# XTAG4.net
KiCad netlist of a schematic drawn in Altium Designer
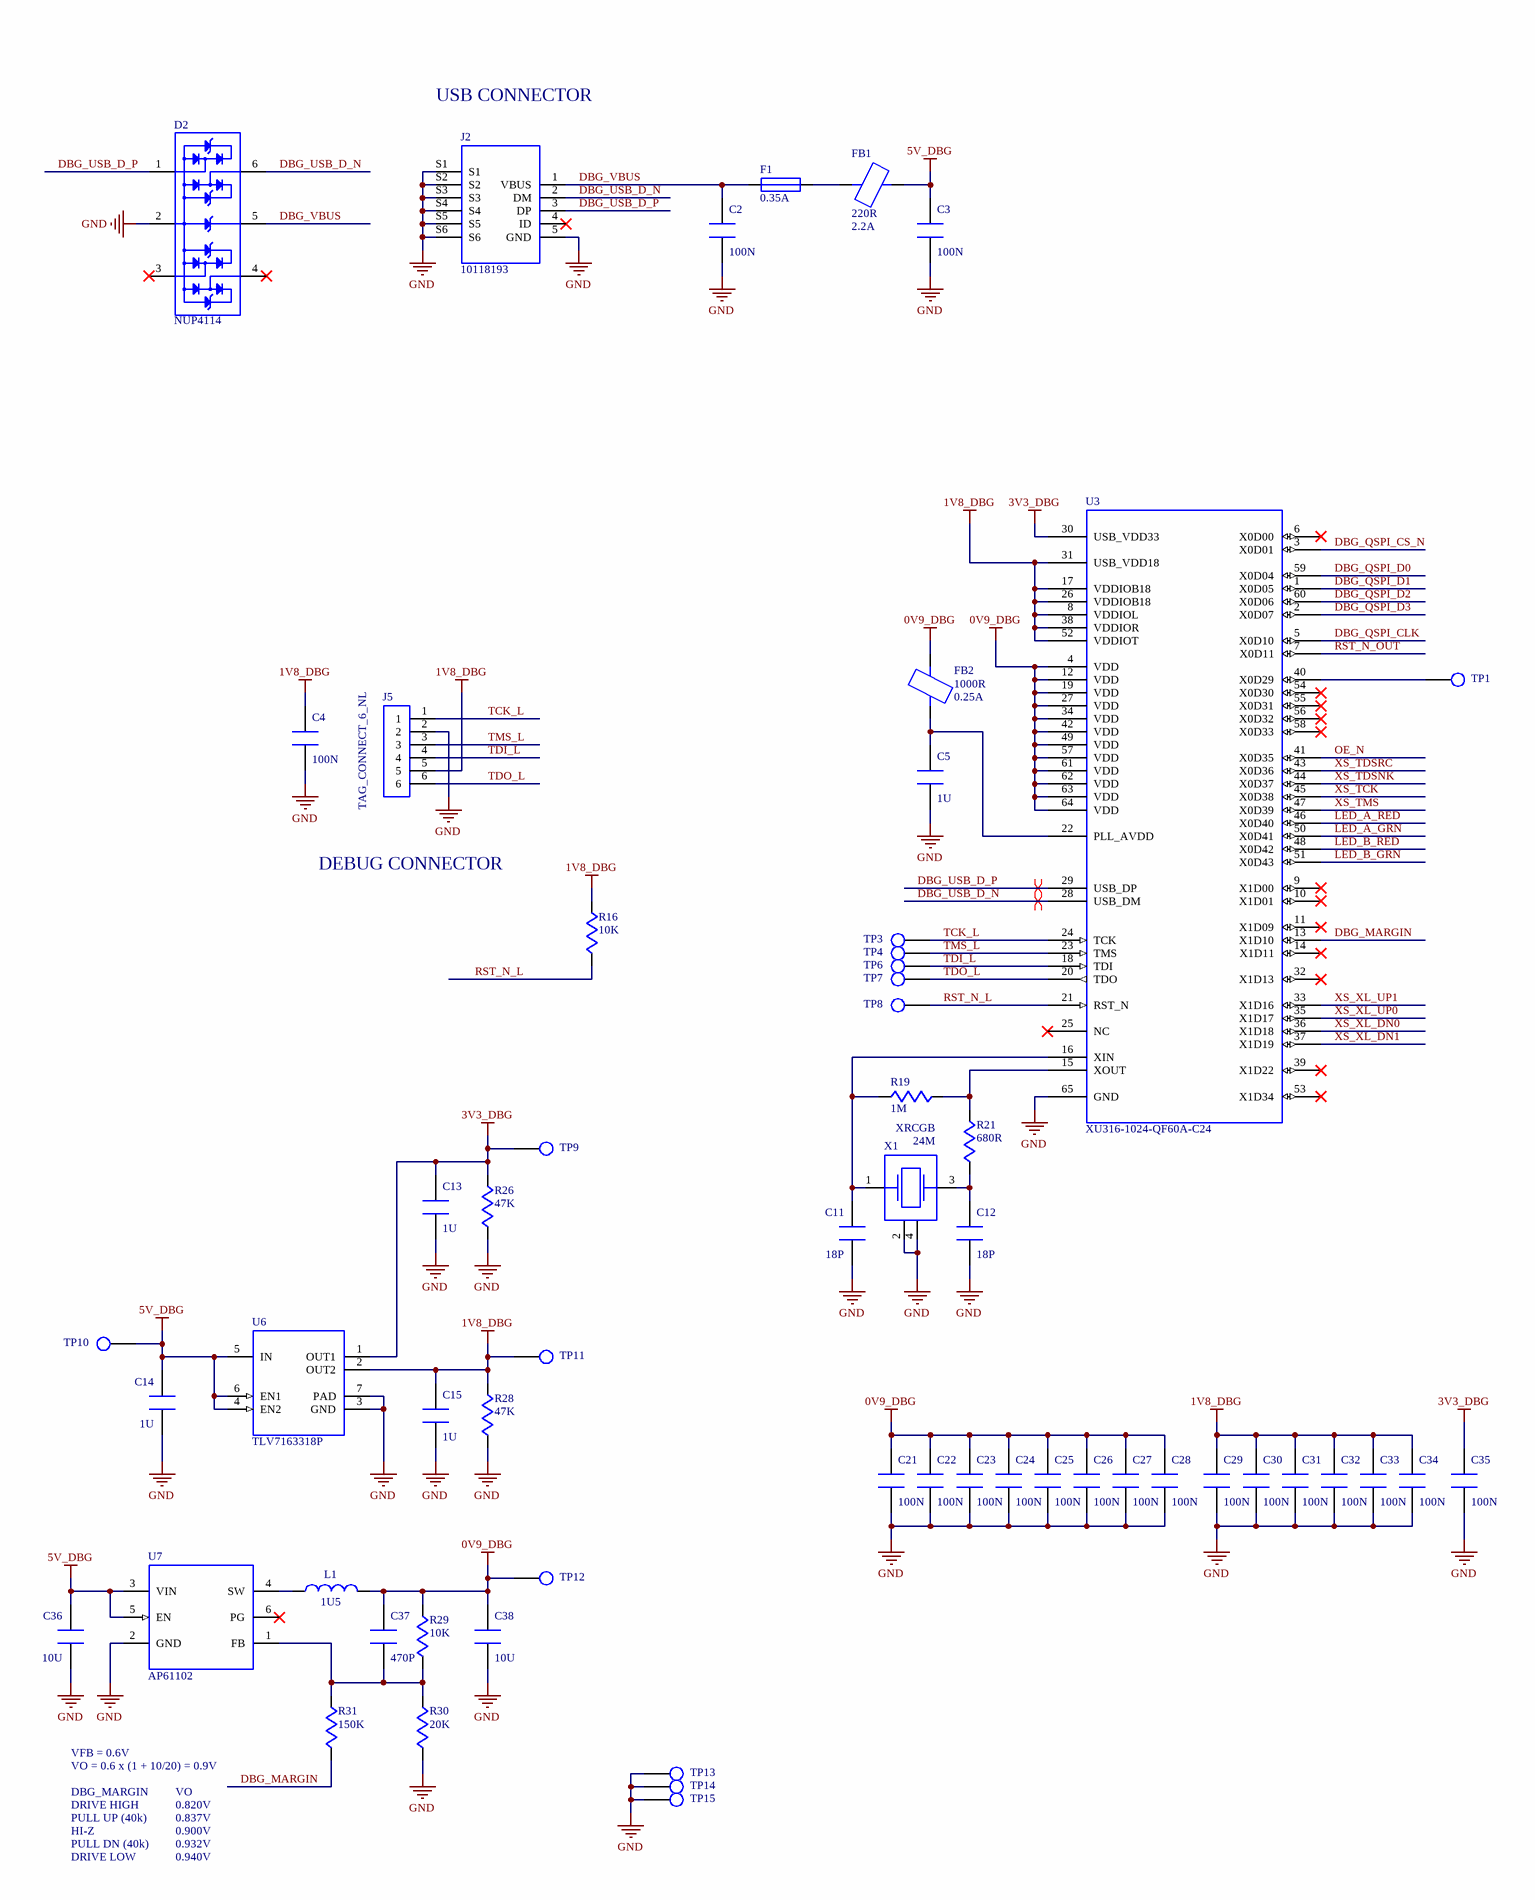
[diagram p0: XTAG4.SchDoc, left]
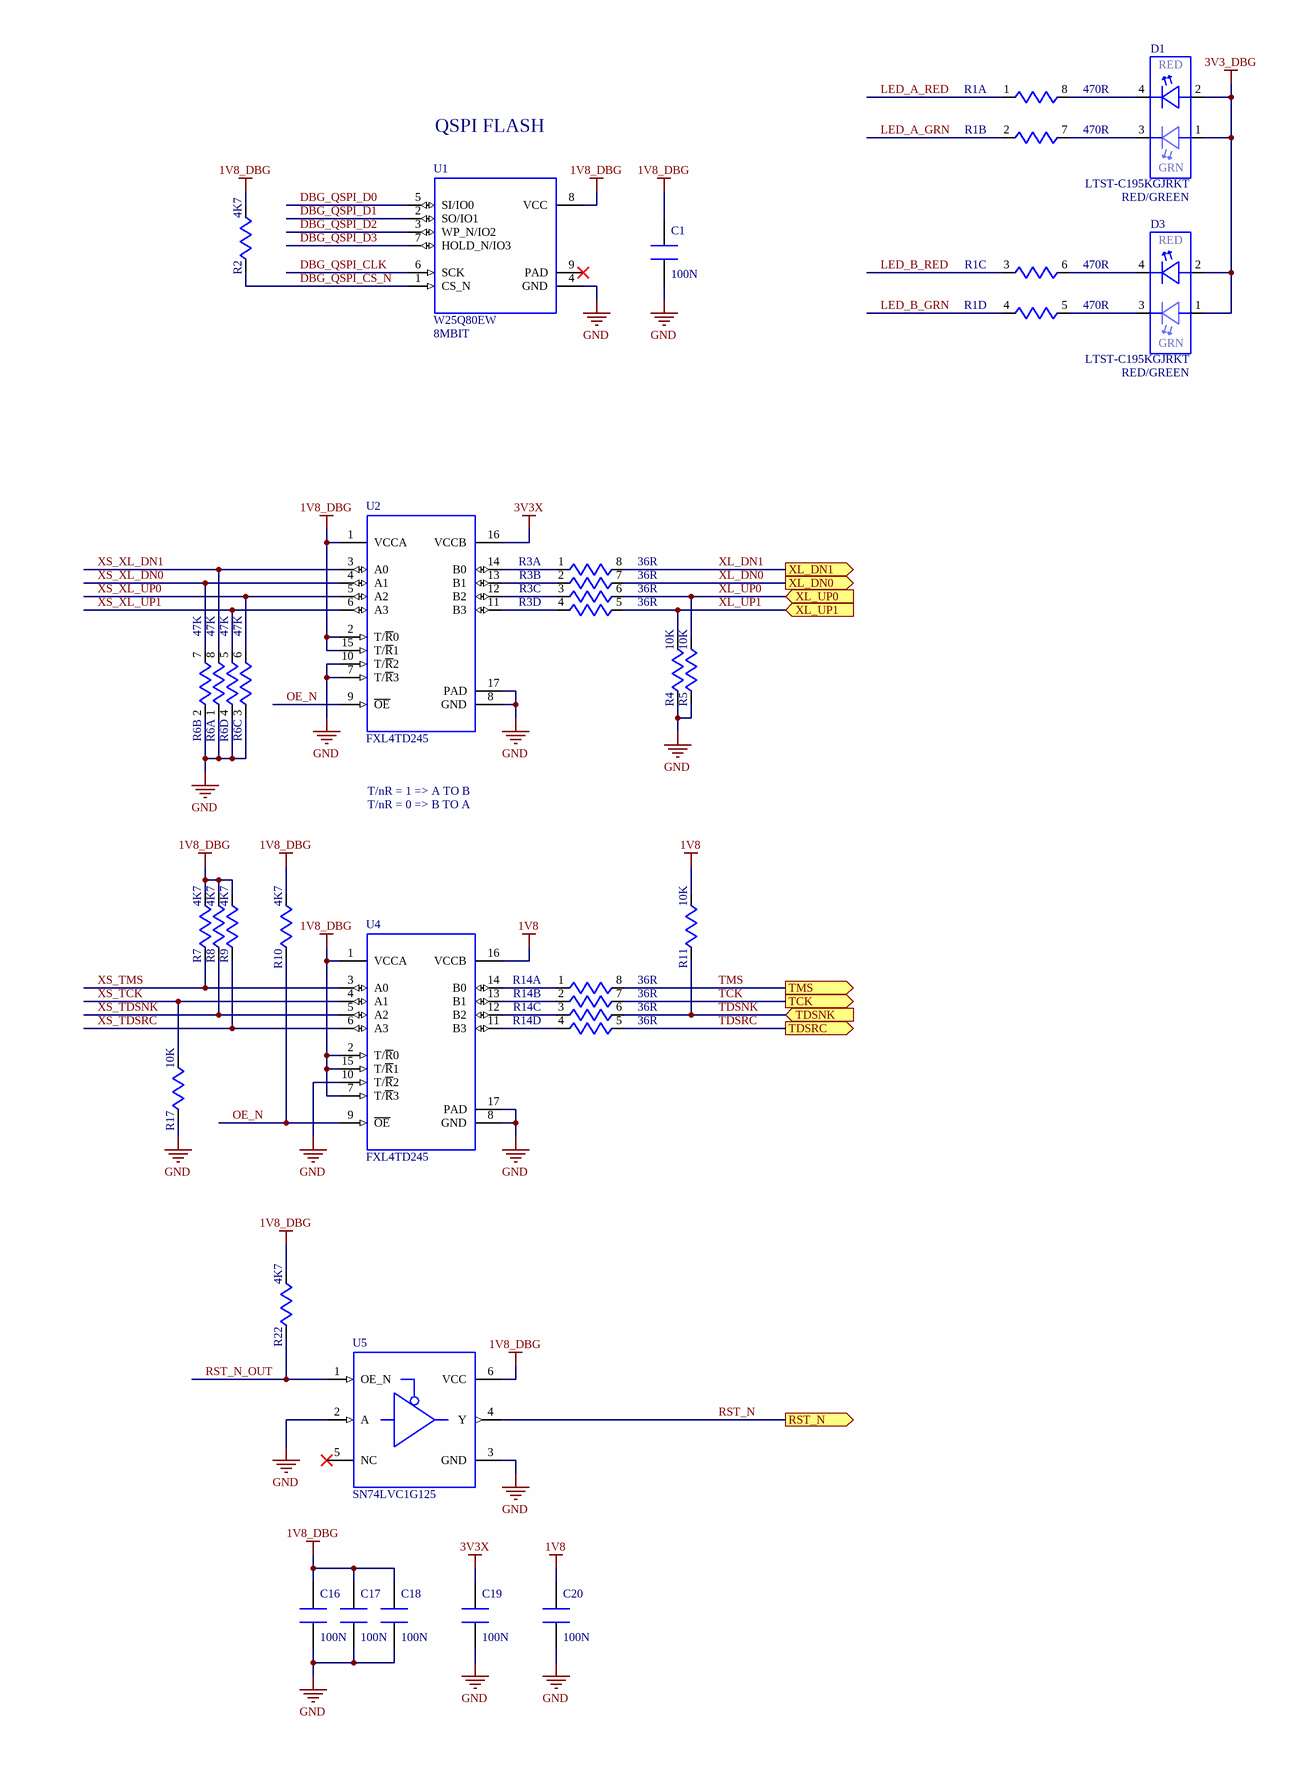
[diagram p1: XTAG4.SchDoc, right]

(export (version "E")
  (design (tool "Eeschema 10.0.6"))
  (components
    (comp (ref "C1")
      (value "100N")
      (footprint "CAPC1005X55N")
      (description "CHIP CAPACITOR, CERAMIC, 100NF, 16V, 10%, X7R, 0402")
      (fields (field (name "PART NUMBER") "STD-06-0048") (field (name "TOLERANCE") "10%"))
      (libsource (lib "JG_StandardLibrary") (part "CAP_NP"))
    )
    (comp (ref "C2")
      (value "100N")
      (footprint "CAPC1005X55N")
      (description "CHIP CAPACITOR, CERAMIC, 100NF, 16V, 10%, X7R, 0402")
      (fields (field (name "PART NUMBER") "STD-06-0048") (field (name "TOLERANCE") "10%"))
      (libsource (lib "JG_StandardLibrary") (part "CAP_NP"))
    )
    (comp (ref "C3")
      (value "100N")
      (footprint "CAPC1005X55N")
      (description "CHIP CAPACITOR, CERAMIC, 100NF, 16V, 10%, X7R, 0402")
      (fields (field (name "PART NUMBER") "STD-06-0048") (field (name "TOLERANCE") "10%"))
      (libsource (lib "JG_StandardLibrary") (part "CAP_NP"))
    )
    (comp (ref "C4")
      (value "100N")
      (footprint "CAPC1005X55N")
      (description "CHIP CAPACITOR, CERAMIC, 100NF, 16V, 10%, X7R, 0402")
      (fields (field (name "PART NUMBER") "STD-06-0048") (field (name "TOLERANCE") "10%"))
      (libsource (lib "JG_StandardLibrary") (part "CAP_NP"))
    )
    (comp (ref "C5")
      (value "1U")
      (footprint "CAPC1005X55N")
      (description "CHIP CAPACITOR, CERAMIC, 1.0UF, 16V, 10%, X5R, 0402")
      (fields (field (name "PART NUMBER") "STD-06-0140") (field (name "TOLERANCE") "20%"))
      (libsource (lib "JG_StandardLibrary") (part "CAP_NP"))
    )
    (comp (ref "C11")
      (value "18P")
      (footprint "CAPC1005X55N")
      (description "CHIP CAPACITOR, CERAMIC, 18PF, 50V, 5%, NP0, 0402")
      (fields (field (name "PART NUMBER") "STD-06-0016") (field (name "TOLERANCE") "5%"))
      (libsource (lib "JG_StandardLibrary") (part "CAP_NP"))
    )
    (comp (ref "C12")
      (value "18P")
      (footprint "CAPC1005X55N")
      (description "CHIP CAPACITOR, CERAMIC, 18PF, 50V, 5%, NP0, 0402")
      (fields (field (name "PART NUMBER") "STD-06-0016") (field (name "TOLERANCE") "5%"))
      (libsource (lib "JG_StandardLibrary") (part "CAP_NP"))
    )
    (comp (ref "C13")
      (value "1U")
      (footprint "CAPC1005X55N")
      (description "CHIP CAPACITOR, CERAMIC, 1.0UF, 16V, 10%, X5R, 0402")
      (fields (field (name "PART NUMBER") "STD-06-0140") (field (name "TOLERANCE") "20%"))
      (libsource (lib "JG_StandardLibrary") (part "CAP_NP"))
    )
    (comp (ref "C14")
      (value "1U")
      (footprint "CAPC1005X55N")
      (description "CHIP CAPACITOR, CERAMIC, 1.0UF, 16V, 10%, X5R, 0402")
      (fields (field (name "PART NUMBER") "STD-06-0140") (field (name "TOLERANCE") "20%"))
      (libsource (lib "JG_StandardLibrary") (part "CAP_NP"))
    )
    (comp (ref "C15")
      (value "1U")
      (footprint "CAPC1005X55N")
      (description "CHIP CAPACITOR, CERAMIC, 1.0UF, 16V, 10%, X5R, 0402")
      (fields (field (name "PART NUMBER") "STD-06-0140") (field (name "TOLERANCE") "20%"))
      (libsource (lib "JG_StandardLibrary") (part "CAP_NP"))
    )
    (comp (ref "C16")
      (value "100N")
      (footprint "CAPC1005X55N")
      (description "CHIP CAPACITOR, CERAMIC, 100NF, 16V, 10%, X7R, 0402")
      (fields (field (name "PART NUMBER") "STD-06-0048") (field (name "TOLERANCE") "10%"))
      (libsource (lib "JG_StandardLibrary") (part "CAP_NP"))
    )
    (comp (ref "C17")
      (value "100N")
      (footprint "CAPC1005X55N")
      (description "CHIP CAPACITOR, CERAMIC, 100NF, 16V, 10%, X7R, 0402")
      (fields (field (name "PART NUMBER") "STD-06-0048") (field (name "TOLERANCE") "10%"))
      (libsource (lib "JG_StandardLibrary") (part "CAP_NP"))
    )
    (comp (ref "C18")
      (value "100N")
      (footprint "CAPC1005X55N")
      (description "CHIP CAPACITOR, CERAMIC, 100NF, 16V, 10%, X7R, 0402")
      (fields (field (name "PART NUMBER") "STD-06-0048") (field (name "TOLERANCE") "10%"))
      (libsource (lib "JG_StandardLibrary") (part "CAP_NP"))
    )
    (comp (ref "C19")
      (value "100N")
      (footprint "CAPC1005X55N")
      (description "CHIP CAPACITOR, CERAMIC, 100NF, 16V, 10%, X7R, 0402")
      (fields (field (name "PART NUMBER") "STD-06-0048") (field (name "TOLERANCE") "10%"))
      (libsource (lib "JG_StandardLibrary") (part "CAP_NP"))
    )
    (comp (ref "C20")
      (value "100N")
      (footprint "CAPC1005X55N")
      (description "CHIP CAPACITOR, CERAMIC, 100NF, 16V, 10%, X7R, 0402")
      (fields (field (name "PART NUMBER") "STD-06-0048") (field (name "TOLERANCE") "10%"))
      (libsource (lib "JG_StandardLibrary") (part "CAP_NP"))
    )
    (comp (ref "C21")
      (value "100N")
      (footprint "CAPC1005X55N")
      (description "CHIP CAPACITOR, CERAMIC, 100NF, 16V, 10%, X7R, 0402")
      (fields (field (name "PART NUMBER") "STD-06-0048") (field (name "TOLERANCE") "10%"))
      (libsource (lib "JG_StandardLibrary") (part "CAP_NP"))
    )
    (comp (ref "C22")
      (value "100N")
      (footprint "CAPC1005X55N")
      (description "CHIP CAPACITOR, CERAMIC, 100NF, 16V, 10%, X7R, 0402")
      (fields (field (name "PART NUMBER") "STD-06-0048") (field (name "TOLERANCE") "10%"))
      (libsource (lib "JG_StandardLibrary") (part "CAP_NP"))
    )
    (comp (ref "C23")
      (value "100N")
      (footprint "CAPC1005X55N")
      (description "CHIP CAPACITOR, CERAMIC, 100NF, 16V, 10%, X7R, 0402")
      (fields (field (name "PART NUMBER") "STD-06-0048") (field (name "TOLERANCE") "10%"))
      (libsource (lib "JG_StandardLibrary") (part "CAP_NP"))
    )
    (comp (ref "C24")
      (value "100N")
      (footprint "CAPC1005X55N")
      (description "CHIP CAPACITOR, CERAMIC, 100NF, 16V, 10%, X7R, 0402")
      (fields (field (name "PART NUMBER") "STD-06-0048") (field (name "TOLERANCE") "10%"))
      (libsource (lib "JG_StandardLibrary") (part "CAP_NP"))
    )
    (comp (ref "C25")
      (value "100N")
      (footprint "CAPC1005X55N")
      (description "CHIP CAPACITOR, CERAMIC, 100NF, 16V, 10%, X7R, 0402")
      (fields (field (name "PART NUMBER") "STD-06-0048") (field (name "TOLERANCE") "10%"))
      (libsource (lib "JG_StandardLibrary") (part "CAP_NP"))
    )
    (comp (ref "C26")
      (value "100N")
      (footprint "CAPC1005X55N")
      (description "CHIP CAPACITOR, CERAMIC, 100NF, 16V, 10%, X7R, 0402")
      (fields (field (name "PART NUMBER") "STD-06-0048") (field (name "TOLERANCE") "10%"))
      (libsource (lib "JG_StandardLibrary") (part "CAP_NP"))
    )
    (comp (ref "C27")
      (value "100N")
      (footprint "CAPC1005X55N")
      (description "CHIP CAPACITOR, CERAMIC, 100NF, 16V, 10%, X7R, 0402")
      (fields (field (name "PART NUMBER") "STD-06-0048") (field (name "TOLERANCE") "10%"))
      (libsource (lib "JG_StandardLibrary") (part "CAP_NP"))
    )
    (comp (ref "C28")
      (value "100N")
      (footprint "CAPC1005X55N")
      (description "CHIP CAPACITOR, CERAMIC, 100NF, 16V, 10%, X7R, 0402")
      (fields (field (name "PART NUMBER") "STD-06-0048") (field (name "TOLERANCE") "10%"))
      (libsource (lib "JG_StandardLibrary") (part "CAP_NP"))
    )
    (comp (ref "C29")
      (value "100N")
      (footprint "CAPC1005X55N")
      (description "CHIP CAPACITOR, CERAMIC, 100NF, 16V, 10%, X7R, 0402")
      (fields (field (name "PART NUMBER") "STD-06-0048") (field (name "TOLERANCE") "10%"))
      (libsource (lib "JG_StandardLibrary") (part "CAP_NP"))
    )
    (comp (ref "C30")
      (value "100N")
      (footprint "CAPC1005X55N")
      (description "CHIP CAPACITOR, CERAMIC, 100NF, 16V, 10%, X7R, 0402")
      (fields (field (name "PART NUMBER") "STD-06-0048") (field (name "TOLERANCE") "10%"))
      (libsource (lib "JG_StandardLibrary") (part "CAP_NP"))
    )
    (comp (ref "C31")
      (value "100N")
      (footprint "CAPC1005X55N")
      (description "CHIP CAPACITOR, CERAMIC, 100NF, 16V, 10%, X7R, 0402")
      (fields (field (name "PART NUMBER") "STD-06-0048") (field (name "TOLERANCE") "10%"))
      (libsource (lib "JG_StandardLibrary") (part "CAP_NP"))
    )
    (comp (ref "C32")
      (value "100N")
      (footprint "CAPC1005X55N")
      (description "CHIP CAPACITOR, CERAMIC, 100NF, 16V, 10%, X7R, 0402")
      (fields (field (name "PART NUMBER") "STD-06-0048") (field (name "TOLERANCE") "10%"))
      (libsource (lib "JG_StandardLibrary") (part "CAP_NP"))
    )
    (comp (ref "C33")
      (value "100N")
      (footprint "CAPC1005X55N")
      (description "CHIP CAPACITOR, CERAMIC, 100NF, 16V, 10%, X7R, 0402")
      (fields (field (name "PART NUMBER") "STD-06-0048") (field (name "TOLERANCE") "10%"))
      (libsource (lib "JG_StandardLibrary") (part "CAP_NP"))
    )
    (comp (ref "C34")
      (value "100N")
      (footprint "CAPC1005X55N")
      (description "CHIP CAPACITOR, CERAMIC, 100NF, 16V, 10%, X7R, 0402")
      (fields (field (name "PART NUMBER") "STD-06-0048") (field (name "TOLERANCE") "10%"))
      (libsource (lib "JG_StandardLibrary") (part "CAP_NP"))
    )
    (comp (ref "C35")
      (value "100N")
      (footprint "CAPC1005X55N")
      (description "CHIP CAPACITOR, CERAMIC, 100NF, 16V, 10%, X7R, 0402")
      (fields (field (name "PART NUMBER") "STD-06-0048") (field (name "TOLERANCE") "10%"))
      (libsource (lib "JG_StandardLibrary") (part "CAP_NP"))
    )
    (comp (ref "C36")
      (value "10U")
      (footprint "CAPC1608X90N")
      (description "CHIP CAPACITOR, CERAMIC, 10UF, 10V, 20%, X5R, 0603")
      (fields (field (name "PART NUMBER") "GEN-03-0043") (field (name "TOLERANCE") "20%"))
      (libsource (lib "JG_GeneralLibrary") (part "CAP_NP"))
    )
    (comp (ref "C37")
      (value "470P")
      (footprint "CAPC1005X55N")
      (description "CHIP CAPACITOR, CERAMIC, 470PF, 50V, 10%, X7R, 0402")
      (fields (field (name "PART NUMBER") "STD-06-0034") (field (name "TOLERANCE") "10%"))
      (libsource (lib "JG_StandardLibrary") (part "CAP_NP"))
    )
    (comp (ref "C38")
      (value "10U")
      (footprint "CAPC1608X90N")
      (description "CHIP CAPACITOR, CERAMIC, 10UF, 10V, 20%, X5R, 0603")
      (fields (field (name "PART NUMBER") "GEN-03-0043") (field (name "TOLERANCE") "20%"))
      (libsource (lib "JG_GeneralLibrary") (part "CAP_NP"))
    )
    (comp (ref "D1")
      (value "LTST-C195KGJRKT")
      (footprint "LED_LITEON_LTST_C195KGJRKT")
      (description "LED, Top View, RED/GREEN, SMD, 0606")
      (fields
        (field (name "PART NUMBER") "GEN-17-0007")
        (field (name "COLOUR") "RED/GREEN")
        (field (name "MANUFACTURER") "Lite-On")
      )
      (libsource (lib "JG_GeneralLibrary") (part "LED_DUAL_SEPARATE_A"))
    )
    (comp (ref "D2")
      (value "NUP4114")
      (footprint "SOT65P210X110-6N")
      (description "ESD Protection Diode Array, 0.6pF, SC-70-6 (SC-88)")
      (fields (field (name "PART NUMBER") "GEN-16-0048") (field (name "MANUFACTURER") "ON Semiconductor"))
      (libsource (lib "JG_GeneralLibrary") (part "DIODE_QUAD_ESD_C"))
    )
    (comp (ref "D3")
      (value "LTST-C195KGJRKT")
      (footprint "LED_LITEON_LTST_C195KGJRKT")
      (description "LED, Top View, RED/GREEN, SMD, 0606")
      (fields
        (field (name "PART NUMBER") "GEN-17-0007")
        (field (name "COLOUR") "RED/GREEN")
        (field (name "MANUFACTURER") "Lite-On")
      )
      (libsource (lib "JG_GeneralLibrary") (part "LED_DUAL_SEPARATE_A"))
    )
    (comp (ref "F1")
      (value "0.35A")
      (footprint "FUSC215X135X75L40N")
      (description "PTC Fuse, SMD, 0.35A hold, 0.75A trip, 6V, 0805")
      (fields (field (name "PART NUMBER") "GEN-21-0009") (field (name "MANUFACTURER") "Bel Fuse"))
      (libsource (lib "JG_GeneralLibrary") (part "FUSE"))
    )
    (comp (ref "FB1")
      (value "220R")
      (footprint "INDC1608X95N")
      (description "Ferrite Bead, 220R AT 100MHz, For Power Lines, AEC-Q200, 0603, 2.2A")
      (fields
        (field (name "PART NUMBER") "GEN-04-0018")
        (field (name "RATED CURRENT") "2.2A")
        (field (name "MANUFACTURER") "Murata")
      )
      (libsource (lib "JG_GeneralLibrary") (part "FERRITE"))
    )
    (comp (ref "FB2")
      (value "1000R")
      (footprint "INDC1005X55N")
      (description "Ferrite Bead, 1000R AT 100MHz, For Signal Lines, 0402, 0.25A")
      (fields
        (field (name "PART NUMBER") "GEN-04-0019")
        (field (name "RATED CURRENT") "0.25A")
        (field (name "MANUFACTURER") "Murata")
      )
      (libsource (lib "JG_GeneralLibrary") (part "FERRITE"))
    )
    (comp (ref "J2")
      (value "10118193")
      (footprint "CON_FCI_10118193")
      (description "USB Micro B Receptacle, Right Angle, SMD w/2 DIP Legs")
      (fields (field (name "PART NUMBER") "GEN-01-0020") (field (name "MANUFACTURER") "FCI"))
      (libsource (lib "JG_GeneralLibrary") (part "FCI_10118193"))
    )
    (comp (ref "J5")
      (value "TAG_CONNECT_6_NL")
      (footprint "CON_TAG_CONNECT_6_NOLEG")
      (description "Connectorless Tag Connect Footprint, 6 pin, No Legs")
      (fields (field (name "PART NUMBER") "GEN-24-0021") (field (name "MANUFACTURER") "NA"))
      (libsource (lib "JG_GeneralLibrary") (part "CON_6PIN_NOBOM"))
    )
    (comp (ref "L1")
      (value "1U5")
      (footprint "INDC2520X120N")
      (description "Power Inductor, 1.5uH, 2.6A, 65mR DCR, 2.5x2.0x1.2mm, SMD")
      (fields (field (name "PART NUMBER") "GEN-05-0025") (field (name "TOLERANCE") "20%"))
      (libsource (lib "JG_GeneralLibrary") (part "INDUCTOR"))
    )
    (comp (ref "R1")
      (value "470R")
      (footprint "RESCAXS50P200X100X55-8N")
      (description "CHIP RESISTOR ARRAY, 4 ELEMENT, 470 OHM, 63mW, 5%, 0804")
      (fields (field (name "PART NUMBER") "STD-09-0014") (field (name "TOLERANCE") "5%"))
      (libsource (lib "JG_StandardLibrary") (part "RES_NET_4_A"))
    )
    (comp (ref "R2")
      (value "4K7")
      (footprint "RESC1005X40N")
      (description "CHIP RESISTOR, 4.7K OHM, 63mW, 1%, 0402")
      (fields (field (name "PART NUMBER") "STD-01-0072") (field (name "TOLERANCE") "1%"))
      (libsource (lib "JG_StandardLibrary") (part "RES"))
    )
    (comp (ref "R3")
      (value "36R")
      (footprint "RESCAXS50P200X100X55-8N")
      (description "CHIP RESISTOR ARRAY, 4 ELEMENT, 36 OHM, 63mW, 5%, 0804")
      (fields (field (name "PART NUMBER") "GEN-02-0026") (field (name "TOLERANCE") "5%"))
      (libsource (lib "JG_GeneralLibrary") (part "RES_NET_4_A"))
    )
    (comp (ref "R4")
      (value "10K")
      (footprint "RESC1005X40N")
      (description "CHIP RESISTOR, 10K OHM, 63mW, 1%, 0402")
      (fields (field (name "PART NUMBER") "STD-01-0080") (field (name "TOLERANCE") "1%"))
      (libsource (lib "JG_StandardLibrary") (part "RES"))
    )
    (comp (ref "R5")
      (value "10K")
      (footprint "RESC1005X40N")
      (description "CHIP RESISTOR, 10K OHM, 63mW, 1%, 0402")
      (fields (field (name "PART NUMBER") "STD-01-0080") (field (name "TOLERANCE") "1%"))
      (libsource (lib "JG_StandardLibrary") (part "RES"))
    )
    (comp (ref "R6")
      (value "47K")
      (footprint "RESCAXS50P200X100X55-8N")
      (description "CHIP RESISTOR ARRAY, 4 ELEMENT, 47K OHM, 63mW, 5%, 0804")
      (fields (field (name "PART NUMBER") "STD-09-0026") (field (name "TOLERANCE") "5%"))
      (libsource (lib "JG_StandardLibrary") (part "RES_NET_4_A"))
    )
    (comp (ref "R7")
      (value "4K7")
      (footprint "RESC1005X40N")
      (description "CHIP RESISTOR, 4.7K OHM, 63mW, 1%, 0402")
      (fields (field (name "PART NUMBER") "STD-01-0072") (field (name "TOLERANCE") "1%"))
      (libsource (lib "JG_StandardLibrary") (part "RES"))
    )
    (comp (ref "R8")
      (value "4K7")
      (footprint "RESC1005X40N")
      (description "CHIP RESISTOR, 4.7K OHM, 63mW, 1%, 0402")
      (fields (field (name "PART NUMBER") "STD-01-0072") (field (name "TOLERANCE") "1%"))
      (libsource (lib "JG_StandardLibrary") (part "RES"))
    )
    (comp (ref "R9")
      (value "4K7")
      (footprint "RESC1005X40N")
      (description "CHIP RESISTOR, 4.7K OHM, 63mW, 1%, 0402")
      (fields (field (name "PART NUMBER") "STD-01-0072") (field (name "TOLERANCE") "1%"))
      (libsource (lib "JG_StandardLibrary") (part "RES"))
    )
    (comp (ref "R10")
      (value "4K7")
      (footprint "RESC1005X40N")
      (description "CHIP RESISTOR, 4.7K OHM, 63mW, 1%, 0402")
      (fields (field (name "PART NUMBER") "STD-01-0072") (field (name "TOLERANCE") "1%"))
      (libsource (lib "JG_StandardLibrary") (part "RES"))
    )
    (comp (ref "R11")
      (value "10K")
      (footprint "RESC1005X40N")
      (description "CHIP RESISTOR, 10K OHM, 63mW, 1%, 0402")
      (fields (field (name "PART NUMBER") "STD-01-0080") (field (name "TOLERANCE") "1%"))
      (libsource (lib "JG_StandardLibrary") (part "RES"))
    )
    (comp (ref "R14")
      (value "36R")
      (footprint "RESCAXS50P200X100X55-8N")
      (description "CHIP RESISTOR ARRAY, 4 ELEMENT, 36 OHM, 63mW, 5%, 0804")
      (fields (field (name "PART NUMBER") "GEN-02-0026") (field (name "TOLERANCE") "5%"))
      (libsource (lib "JG_GeneralLibrary") (part "RES_NET_4_A"))
    )
    (comp (ref "R16")
      (value "10K")
      (footprint "RESC1005X40N")
      (description "CHIP RESISTOR, 10K OHM, 63mW, 1%, 0402")
      (fields (field (name "PART NUMBER") "STD-01-0080") (field (name "TOLERANCE") "1%"))
      (libsource (lib "JG_StandardLibrary") (part "RES"))
    )
    (comp (ref "R17")
      (value "10K")
      (footprint "RESC1005X40N")
      (description "CHIP RESISTOR, 10K OHM, 63mW, 1%, 0402")
      (fields (field (name "PART NUMBER") "STD-01-0080") (field (name "TOLERANCE") "1%"))
      (libsource (lib "JG_StandardLibrary") (part "RES"))
    )
    (comp (ref "R19")
      (value "1M")
      (footprint "RESC1005X40N")
      (description "CHIP RESISTOR, 1.0M OHM, 63mW, 5%, 0402")
      (fields (field (name "PART NUMBER") "STD-01-0128") (field (name "TOLERANCE") "5%"))
      (libsource (lib "JG_StandardLibrary") (part "RES"))
    )
    (comp (ref "R21")
      (value "680R")
      (footprint "RESC1005X40N")
      (description "CHIP RESISTOR, 680 OHM, 63mW, 1%, 0402")
      (fields (field (name "PART NUMBER") "STD-01-0052") (field (name "TOLERANCE") "1%"))
      (libsource (lib "JG_StandardLibrary") (part "RES"))
    )
    (comp (ref "R22")
      (value "4K7")
      (footprint "RESC1005X40N")
      (description "CHIP RESISTOR, 4.7K OHM, 63mW, 1%, 0402")
      (fields (field (name "PART NUMBER") "STD-01-0072") (field (name "TOLERANCE") "1%"))
      (libsource (lib "JG_StandardLibrary") (part "RES"))
    )
    (comp (ref "R26")
      (value "47K")
      (footprint "RESC1005X40N")
      (description "CHIP RESISTOR, 47K OHM, 63mW, 1%, 0402")
      (fields (field (name "PART NUMBER") "STD-01-0096") (field (name "TOLERANCE") "1%"))
      (libsource (lib "JG_StandardLibrary") (part "RES"))
    )
    (comp (ref "R28")
      (value "47K")
      (footprint "RESC1005X40N")
      (description "CHIP RESISTOR, 47K OHM, 63mW, 1%, 0402")
      (fields (field (name "PART NUMBER") "STD-01-0096") (field (name "TOLERANCE") "1%"))
      (libsource (lib "JG_StandardLibrary") (part "RES"))
    )
    (comp (ref "R29")
      (value "10K")
      (footprint "RESC1005X40N")
      (description "CHIP RESISTOR, 10K OHM, 63mW, 1%, 0402")
      (fields (field (name "PART NUMBER") "STD-01-0080") (field (name "TOLERANCE") "1%"))
      (libsource (lib "JG_StandardLibrary") (part "RES"))
    )
    (comp (ref "R30")
      (value "20K")
      (footprint "RESC1005X40N")
      (description "CHIP RESISTOR, 20K OHM, 63mW, 1%, 0402")
      (fields (field (name "PART NUMBER") "STD-01-0087") (field (name "TOLERANCE") "1%"))
      (libsource (lib "JG_StandardLibrary") (part "RES"))
    )
    (comp (ref "R31")
      (value "150K")
      (footprint "RESC1005X40N")
      (description "CHIP RESISTOR, 150K OHM, 63mW, 1%, 0402")
      (fields (field (name "PART NUMBER") "STD-01-0108") (field (name "TOLERANCE") "1%"))
      (libsource (lib "JG_StandardLibrary") (part "RES"))
    )
    (comp (ref "TP1")
      (value "TESTPOINT")
      (footprint "TESTPOINT_SMD_1MM")
      (description "Testpoint, SMD, 1mm")
      (fields (field (name "PART NUMBER") "GEN-24-0003") (field (name "MANUFACTURER") "NA"))
      (libsource (lib "JG_GeneralLibrary") (part "TESTPOINT"))
    )
    (comp (ref "TP3")
      (value "TESTPOINT")
      (footprint "TESTPOINT_SMD_1.2MM")
      (description "Testpoint, SMD, 1.2mm")
      (fields (field (name "PART NUMBER") "GEN-24-0014") (field (name "MANUFACTURER") "NA"))
      (libsource (lib "JG_GeneralLibrary") (part "TESTPOINT"))
    )
    (comp (ref "TP4")
      (value "TESTPOINT")
      (footprint "TESTPOINT_SMD_1.2MM")
      (description "Testpoint, SMD, 1.2mm")
      (fields (field (name "PART NUMBER") "GEN-24-0014") (field (name "MANUFACTURER") "NA"))
      (libsource (lib "JG_GeneralLibrary") (part "TESTPOINT"))
    )
    (comp (ref "TP6")
      (value "TESTPOINT")
      (footprint "TESTPOINT_SMD_1.2MM")
      (description "Testpoint, SMD, 1.2mm")
      (fields (field (name "PART NUMBER") "GEN-24-0014") (field (name "MANUFACTURER") "NA"))
      (libsource (lib "JG_GeneralLibrary") (part "TESTPOINT"))
    )
    (comp (ref "TP7")
      (value "TESTPOINT")
      (footprint "TESTPOINT_SMD_1.2MM")
      (description "Testpoint, SMD, 1.2mm")
      (fields (field (name "PART NUMBER") "GEN-24-0014") (field (name "MANUFACTURER") "NA"))
      (libsource (lib "JG_GeneralLibrary") (part "TESTPOINT"))
    )
    (comp (ref "TP8")
      (value "TESTPOINT")
      (footprint "TESTPOINT_SMD_1.2MM")
      (description "Testpoint, SMD, 1.2mm")
      (fields (field (name "PART NUMBER") "GEN-24-0014") (field (name "MANUFACTURER") "NA"))
      (libsource (lib "JG_GeneralLibrary") (part "TESTPOINT"))
    )
    (comp (ref "TP9")
      (value "TESTPOINT")
      (footprint "TESTPOINT_SMD_1.2MM")
      (description "Testpoint, SMD, 1.2mm")
      (fields (field (name "PART NUMBER") "GEN-24-0014") (field (name "MANUFACTURER") "NA"))
      (libsource (lib "JG_GeneralLibrary") (part "TESTPOINT"))
    )
    (comp (ref "TP10")
      (value "TESTPOINT")
      (footprint "TESTPOINT_SMD_1.2MM")
      (description "Testpoint, SMD, 1.2mm")
      (fields (field (name "PART NUMBER") "GEN-24-0014") (field (name "MANUFACTURER") "NA"))
      (libsource (lib "JG_GeneralLibrary") (part "TESTPOINT"))
    )
    (comp (ref "TP11")
      (value "TESTPOINT")
      (footprint "TESTPOINT_SMD_1.2MM")
      (description "Testpoint, SMD, 1.2mm")
      (fields (field (name "PART NUMBER") "GEN-24-0014") (field (name "MANUFACTURER") "NA"))
      (libsource (lib "JG_GeneralLibrary") (part "TESTPOINT"))
    )
    (comp (ref "TP12")
      (value "TESTPOINT")
      (footprint "TESTPOINT_SMD_1.2MM")
      (description "Testpoint, SMD, 1.2mm")
      (fields (field (name "PART NUMBER") "GEN-24-0014") (field (name "MANUFACTURER") "NA"))
      (libsource (lib "JG_GeneralLibrary") (part "TESTPOINT"))
    )
    (comp (ref "TP13")
      (value "TESTPOINT")
      (footprint "TESTPOINT_SMD_1.2MM")
      (description "Testpoint, SMD, 1.2mm")
      (fields (field (name "PART NUMBER") "GEN-24-0014") (field (name "MANUFACTURER") "NA"))
      (libsource (lib "JG_GeneralLibrary") (part "TESTPOINT"))
    )
    (comp (ref "TP14")
      (value "TESTPOINT")
      (footprint "TESTPOINT_SMD_1.2MM")
      (description "Testpoint, SMD, 1.2mm")
      (fields (field (name "PART NUMBER") "GEN-24-0014") (field (name "MANUFACTURER") "NA"))
      (libsource (lib "JG_GeneralLibrary") (part "TESTPOINT"))
    )
    (comp (ref "TP15")
      (value "TESTPOINT")
      (footprint "TESTPOINT_SMD_1.2MM")
      (description "Testpoint, SMD, 1.2mm")
      (fields (field (name "PART NUMBER") "GEN-24-0014") (field (name "MANUFACTURER") "NA"))
      (libsource (lib "JG_GeneralLibrary") (part "TESTPOINT"))
    )
    (comp (ref "U1")
      (value "W25Q80EW")
      (footprint "SON9P50_200X300X60L45X25T160X20N")
      (description "Memory, Flash, SPI, Multi-IO, 8Mb (4Kx256), 1.65V to 1.95V, USON-8 (2x3mm)")
      (fields
        (field (name "PART NUMBER") "GEN-12-0023")
        (field (name "MEMORY SIZE") "8MBIT")
        (field (name "MANUFACTURER") "Winbond")
      )
      (libsource (lib "JG_GeneralLibrary") (part "SPI_FLASH_MULTI_C"))
    )
    (comp (ref "U2")
      (value "FXL4TD245")
      (footprint "IC_NXP_DHVQFN16")
      (description "Configurable Dual-Voltage Supply Translator, 4 bit, DQFN16")
      (fields (field (name "PART NUMBER") "GEN-11-0017") (field (name "MANUFACTURER") "Fairchild"))
      (libsource (lib "JG_GeneralLibrary") (part "FXL4TD245_A"))
    )
    (comp (ref "U3")
      (value "XU316-1024-QF60A-C24")
      (footprint "IC_XMOS_PX_QFN60A_NEWPADDLE")
      (description "Processor, xcore.ai, 2400MIPS, 1.8V VDDIO, 60QFN")
      (fields (field (name "PART NUMBER") "GEN-08-0033") (field (name "MANUFACTURER") "XMOS"))
      (libsource (lib "JG_GeneralLibrary") (part "XMOS_XU316_1024_QF60A"))
    )
    (comp (ref "U4")
      (value "FXL4TD245")
      (footprint "IC_NXP_DHVQFN16")
      (description "Configurable Dual-Voltage Supply Translator, 4 bit, DQFN16")
      (fields (field (name "PART NUMBER") "GEN-11-0017") (field (name "MANUFACTURER") "Fairchild"))
      (libsource (lib "JG_GeneralLibrary") (part "FXL4TD245_A"))
    )
    (comp (ref "U5")
      (value "SN74LVC1G125")
      (footprint "TI_R_PUSON_N6")
      (description "Single Buffer with 3-State Output, LVC Series, SON6")
      (fields (field (name "PART NUMBER") "GEN-11-0049") (field (name "MANUFACTURER") "Texas Instruments"))
      (libsource (lib "JG_GeneralLibrary") (part "SINGLEGATE_125_B"))
    )
    (comp (ref "U6")
      (value "TLV7163318P")
      (footprint "TI_S_PX2SON_N6")
      (description "Voltage Regulator, Dual, 3.3V/1.8V, 150mA, Low Iq, Low Dropout, X2SON-6")
      (fields (field (name "PART NUMBER") "GEN-14-0057") (field (name "MANUFACTURER") "Texas Instruments"))
      (libsource (lib "JG_GeneralLibrary") (part "VREG_FIXED_DUAL_6_A"))
    )
    (comp (ref "U7")
      (value "AP61102")
      (footprint "ICSOFL6P50_160X160X60L30X21N")
      (description "DC-DC Synchronous Buck Converter, Adjustable, PFM/PWM, Power Good, 2.2MHz, 1A, SOT563")
      (fields (field (name "PART NUMBER") "GEN-14-0064") (field (name "MANUFACTURER") "Diodes Incorporated"))
      (libsource (lib "JG_GeneralLibrary") (part "DIODES_AP61102"))
    )
    (comp (ref "X1")
      (value "XRCGB")
      (footprint "OSCCC200X160X70N")
      (description "Crystal, 24MHz, Freq Tol. ±8ppm, Freq Stab. ±12ppm, CL 10pF, Max ESR 70 Ohm, 2.0x1.6mm SMD")
      (fields
        (field (name "FREQUENCY") "24M")
        (field (name "PART NUMBER") "GEN-15-0038")
        (field (name "MANUFACTURER") "Murata")
      )
      (libsource (lib "JG_GeneralLibrary") (part "CRYSTAL_4PIN_A"))
    )
  )
  (nets
    (net (code "1") (name "/DBG_MARGIN") (class "Default")
      (node (ref "R31") (pin "1") (pinfunction "1_1") (pintype "passive"))
      (node (ref "U3") (pin "13") (pinfunction "X1D10_13") (pintype "bidirectional"))
    )
    (net (code "2") (name "/DBG_QSPI_CLK") (class "Default")
      (node (ref "U1") (pin "6") (pinfunction "SCK_6") (pintype "input"))
      (node (ref "U3") (pin "5") (pinfunction "X0D10_5") (pintype "bidirectional"))
    )
    (net (code "3") (name "/DBG_QSPI_CS_N") (class "Default")
      (node (ref "R2") (pin "1") (pinfunction "1_1") (pintype "passive"))
      (node (ref "U1") (pin "1") (pinfunction "CS_N_1") (pintype "input"))
      (node (ref "U3") (pin "3") (pinfunction "X0D01_3") (pintype "bidirectional"))
    )
    (net (code "4") (name "/DBG_QSPI_D0") (class "Default")
      (node (ref "U1") (pin "5") (pinfunction "SI/IO0_5") (pintype "bidirectional"))
      (node (ref "U3") (pin "59") (pinfunction "X0D04_59") (pintype "bidirectional"))
    )
    (net (code "5") (name "/DBG_QSPI_D1") (class "Default")
      (node (ref "U1") (pin "2") (pinfunction "SO/IO1_2") (pintype "bidirectional"))
      (node (ref "U3") (pin "1") (pinfunction "X0D05_1") (pintype "bidirectional"))
    )
    (net (code "6") (name "/DBG_QSPI_D2") (class "Default")
      (node (ref "U1") (pin "3") (pinfunction "WP_N/IO2_3") (pintype "bidirectional"))
      (node (ref "U3") (pin "60") (pinfunction "X0D06_60") (pintype "bidirectional"))
    )
    (net (code "7") (name "/DBG_QSPI_D3") (class "Default")
      (node (ref "U1") (pin "7") (pinfunction "HOLD_N/IO3_7") (pintype "bidirectional"))
      (node (ref "U3") (pin "2") (pinfunction "X0D07_2") (pintype "bidirectional"))
    )
    (net (code "8") (name "/DBG_USB_D_N") (class "Default")
      (node (ref "D2") (pin "6") (pinfunction "6_6") (pintype "passive"))
      (node (ref "J2") (pin "2") (pinfunction "DM_2") (pintype "passive"))
      (node (ref "U3") (pin "28") (pinfunction "USB_DM_28") (pintype "passive"))
    )
    (net (code "9") (name "/DBG_USB_D_P") (class "Default")
      (node (ref "D2") (pin "1") (pinfunction "1_1") (pintype "passive"))
      (node (ref "J2") (pin "3") (pinfunction "DP_3") (pintype "passive"))
      (node (ref "U3") (pin "29") (pinfunction "USB_DP_29") (pintype "passive"))
    )
    (net (code "10") (name "/DBG_VBUS") (class "Default")
      (node (ref "C2") (pin "1") (pinfunction "1_1") (pintype "passive"))
      (node (ref "D2") (pin "5") (pinfunction "5_5") (pintype "passive"))
      (node (ref "F1") (pin "1") (pinfunction "T1_1") (pintype "passive"))
      (node (ref "J2") (pin "1") (pinfunction "VBUS_1") (pintype "passive"))
    )
    (net (code "11") (name "/LED_A_GRN") (class "Default")
      (node (ref "R1") (pin "2") (pinfunction "2_2") (pintype "passive"))
      (node (ref "U3") (pin "50") (pinfunction "X0D41_50") (pintype "bidirectional"))
    )
    (net (code "12") (name "/LED_A_RED") (class "Default")
      (node (ref "R1") (pin "1") (pinfunction "1_1") (pintype "passive"))
      (node (ref "U3") (pin "46") (pinfunction "X0D40_46") (pintype "bidirectional"))
    )
    (net (code "13") (name "/LED_B_GRN") (class "Default")
      (node (ref "R1") (pin "4") (pinfunction "4_4") (pintype "passive"))
      (node (ref "U3") (pin "51") (pinfunction "X0D43_51") (pintype "bidirectional"))
    )
    (net (code "14") (name "/LED_B_RED") (class "Default")
      (node (ref "R1") (pin "3") (pinfunction "3_3") (pintype "passive"))
      (node (ref "U3") (pin "48") (pinfunction "X0D42_48") (pintype "bidirectional"))
    )
    (net (code "15") (name "/OE_N") (class "Default")
      (node (ref "R10") (pin "1") (pinfunction "1_1") (pintype "passive"))
      (node (ref "U2") (pin "9") (pinfunction "~{OE}_9") (pintype "input"))
      (node (ref "U3") (pin "41") (pinfunction "X0D35_41") (pintype "bidirectional"))
      (node (ref "U4") (pin "9") (pinfunction "~{OE}_9") (pintype "input"))
    )
    (net (code "16") (name "/RST_N") (class "Default")
      (node (ref "U5") (pin "4") (pinfunction "Y_4") (pintype "output"))
    )
    (net (code "17") (name "/RST_N_L") (class "Default")
      (node (ref "R16") (pin "1") (pinfunction "1_1") (pintype "passive"))
      (node (ref "TP8") (pin "1") (pinfunction "1_1") (pintype "passive"))
      (node (ref "U3") (pin "21") (pinfunction "RST_N_21") (pintype "input"))
    )
    (net (code "18") (name "/RST_N_OUT") (class "Default")
      (node (ref "R22") (pin "1") (pinfunction "1_1") (pintype "passive"))
      (node (ref "U3") (pin "7") (pinfunction "X0D11_7") (pintype "bidirectional"))
      (node (ref "U5") (pin "1") (pinfunction "OE_N_1") (pintype "input"))
    )
    (net (code "19") (name "/TCK") (class "Default")
      (node (ref "R14") (pin "7") (pinfunction "7_7") (pintype "passive"))
    )
    (net (code "20") (name "/TCK_L") (class "Default")
      (node (ref "J5") (pin "1") (pinfunction "1_1") (pintype "passive"))
      (node (ref "TP3") (pin "1") (pinfunction "1_1") (pintype "passive"))
      (node (ref "U3") (pin "24") (pinfunction "TCK_24") (pintype "input"))
    )
    (net (code "21") (name "/TDI_L") (class "Default")
      (node (ref "J5") (pin "4") (pinfunction "4_4") (pintype "passive"))
      (node (ref "TP6") (pin "1") (pinfunction "1_1") (pintype "passive"))
      (node (ref "U3") (pin "18") (pinfunction "TDI_18") (pintype "input"))
    )
    (net (code "22") (name "/TDO_L") (class "Default")
      (node (ref "J5") (pin "6") (pinfunction "6_6") (pintype "passive"))
      (node (ref "TP7") (pin "1") (pinfunction "1_1") (pintype "passive"))
      (node (ref "U3") (pin "20") (pinfunction "TDO_20") (pintype "output"))
    )
    (net (code "23") (name "/TDSNK") (class "Default")
      (node (ref "R11") (pin "1") (pinfunction "1_1") (pintype "passive"))
      (node (ref "R14") (pin "6") (pinfunction "6_6") (pintype "passive"))
    )
    (net (code "24") (name "/TDSRC") (class "Default")
      (node (ref "R14") (pin "5") (pinfunction "5_5") (pintype "passive"))
    )
    (net (code "25") (name "/TMS") (class "Default")
      (node (ref "R14") (pin "8") (pinfunction "8_8") (pintype "passive"))
    )
    (net (code "26") (name "/TMS_L") (class "Default")
      (node (ref "J5") (pin "3") (pinfunction "3_3") (pintype "passive"))
      (node (ref "TP4") (pin "1") (pinfunction "1_1") (pintype "passive"))
      (node (ref "U3") (pin "23") (pinfunction "TMS_23") (pintype "input"))
    )
    (net (code "27") (name "/XL_DN0") (class "Default")
      (node (ref "R3") (pin "7") (pinfunction "7_7") (pintype "passive"))
    )
    (net (code "28") (name "/XL_DN1") (class "Default")
      (node (ref "R3") (pin "8") (pinfunction "8_8") (pintype "passive"))
    )
    (net (code "29") (name "/XL_UP0") (class "Default")
      (node (ref "R3") (pin "6") (pinfunction "6_6") (pintype "passive"))
      (node (ref "R5") (pin "2") (pinfunction "2_2") (pintype "passive"))
    )
    (net (code "30") (name "/XL_UP1") (class "Default")
      (node (ref "R3") (pin "5") (pinfunction "5_5") (pintype "passive"))
      (node (ref "R4") (pin "2") (pinfunction "2_2") (pintype "passive"))
    )
    (net (code "31") (name "/XS_TCK") (class "Default")
      (node (ref "R17") (pin "2") (pinfunction "2_2") (pintype "passive"))
      (node (ref "U3") (pin "45") (pinfunction "X0D38_45") (pintype "bidirectional"))
      (node (ref "U4") (pin "4") (pinfunction "A1_4") (pintype "bidirectional"))
    )
    (net (code "32") (name "/XS_TDSNK") (class "Default")
      (node (ref "R8") (pin "1") (pinfunction "1_1") (pintype "passive"))
      (node (ref "U3") (pin "44") (pinfunction "X0D37_44") (pintype "bidirectional"))
      (node (ref "U4") (pin "5") (pinfunction "A2_5") (pintype "bidirectional"))
    )
    (net (code "33") (name "/XS_TDSRC") (class "Default")
      (node (ref "R9") (pin "1") (pinfunction "1_1") (pintype "passive"))
      (node (ref "U3") (pin "43") (pinfunction "X0D36_43") (pintype "bidirectional"))
      (node (ref "U4") (pin "6") (pinfunction "A3_6") (pintype "bidirectional"))
    )
    (net (code "34") (name "/XS_TMS") (class "Default")
      (node (ref "R7") (pin "1") (pinfunction "1_1") (pintype "passive"))
      (node (ref "U3") (pin "47") (pinfunction "X0D39_47") (pintype "bidirectional"))
      (node (ref "U4") (pin "3") (pinfunction "A0_3") (pintype "bidirectional"))
    )
    (net (code "35") (name "/XS_XL_DN0") (class "Default")
      (node (ref "R6") (pin "7") (pinfunction "7_7") (pintype "passive"))
      (node (ref "U2") (pin "4") (pinfunction "A1_4") (pintype "bidirectional"))
      (node (ref "U3") (pin "36") (pinfunction "X1D18_36") (pintype "bidirectional"))
    )
    (net (code "36") (name "/XS_XL_DN1") (class "Default")
      (node (ref "R6") (pin "8") (pinfunction "8_8") (pintype "passive"))
      (node (ref "U2") (pin "3") (pinfunction "A0_3") (pintype "bidirectional"))
      (node (ref "U3") (pin "37") (pinfunction "X1D19_37") (pintype "bidirectional"))
    )
    (net (code "37") (name "/XS_XL_UP0") (class "Default")
      (node (ref "R6") (pin "6") (pinfunction "6_6") (pintype "passive"))
      (node (ref "U2") (pin "5") (pinfunction "A2_5") (pintype "bidirectional"))
      (node (ref "U3") (pin "35") (pinfunction "X1D17_35") (pintype "bidirectional"))
    )
    (net (code "38") (name "/XS_XL_UP1") (class "Default")
      (node (ref "R6") (pin "5") (pinfunction "5_5") (pintype "passive"))
      (node (ref "U2") (pin "6") (pinfunction "A3_6") (pintype "bidirectional"))
      (node (ref "U3") (pin "33") (pinfunction "X1D16_33") (pintype "bidirectional"))
    )
    (net (code "39") (name "0V9_DBG") (class "Default")
      (node (ref "C21") (pin "1") (pinfunction "1_1") (pintype "passive"))
      (node (ref "C22") (pin "1") (pinfunction "1_1") (pintype "passive"))
      (node (ref "C23") (pin "1") (pinfunction "1_1") (pintype "passive"))
      (node (ref "C24") (pin "1") (pinfunction "1_1") (pintype "passive"))
      (node (ref "C25") (pin "1") (pinfunction "1_1") (pintype "passive"))
      (node (ref "C26") (pin "1") (pinfunction "1_1") (pintype "passive"))
      (node (ref "C27") (pin "1") (pinfunction "1_1") (pintype "passive"))
      (node (ref "C28") (pin "1") (pinfunction "1_1") (pintype "passive"))
      (node (ref "C37") (pin "1") (pinfunction "1_1") (pintype "passive"))
      (node (ref "C38") (pin "1") (pinfunction "1_1") (pintype "passive"))
      (node (ref "FB2") (pin "2") (pinfunction "2_2") (pintype "passive"))
      (node (ref "L1") (pin "2") (pinfunction "2_2") (pintype "passive"))
      (node (ref "R29") (pin "2") (pinfunction "2_2") (pintype "passive"))
      (node (ref "TP12") (pin "1") (pinfunction "1_1") (pintype "passive"))
      (node (ref "U3") (pin "12") (pinfunction "VDD_12") (pintype "power_in"))
      (node (ref "U3") (pin "19") (pinfunction "VDD_19") (pintype "power_in"))
      (node (ref "U3") (pin "27") (pinfunction "VDD_27") (pintype "power_in"))
      (node (ref "U3") (pin "34") (pinfunction "VDD_34") (pintype "power_in"))
      (node (ref "U3") (pin "4") (pinfunction "VDD_4") (pintype "power_in"))
      (node (ref "U3") (pin "42") (pinfunction "VDD_42") (pintype "power_in"))
      (node (ref "U3") (pin "49") (pinfunction "VDD_49") (pintype "power_in"))
      (node (ref "U3") (pin "57") (pinfunction "VDD_57") (pintype "power_in"))
      (node (ref "U3") (pin "61") (pinfunction "VDD_61") (pintype "power_in"))
      (node (ref "U3") (pin "62") (pinfunction "VDD_62") (pintype "power_in"))
      (node (ref "U3") (pin "63") (pinfunction "VDD_63") (pintype "power_in"))
      (node (ref "U3") (pin "64") (pinfunction "VDD_64") (pintype "power_in"))
    )
    (net (code "40") (name "1V8") (class "Default")
      (node (ref "C20") (pin "1") (pinfunction "1_1") (pintype "passive"))
      (node (ref "R11") (pin "2") (pinfunction "2_2") (pintype "passive"))
      (node (ref "U4") (pin "16") (pinfunction "VCCB_16") (pintype "power_in"))
    )
    (net (code "41") (name "1V8_DBG") (class "Default")
      (node (ref "C1") (pin "1") (pinfunction "1_1") (pintype "passive"))
      (node (ref "C15") (pin "1") (pinfunction "1_1") (pintype "passive"))
      (node (ref "C16") (pin "1") (pinfunction "1_1") (pintype "passive"))
      (node (ref "C17") (pin "1") (pinfunction "1_1") (pintype "passive"))
      (node (ref "C18") (pin "1") (pinfunction "1_1") (pintype "passive"))
      (node (ref "C29") (pin "1") (pinfunction "1_1") (pintype "passive"))
      (node (ref "C30") (pin "1") (pinfunction "1_1") (pintype "passive"))
      (node (ref "C31") (pin "1") (pinfunction "1_1") (pintype "passive"))
      (node (ref "C32") (pin "1") (pinfunction "1_1") (pintype "passive"))
      (node (ref "C33") (pin "1") (pinfunction "1_1") (pintype "passive"))
      (node (ref "C34") (pin "1") (pinfunction "1_1") (pintype "passive"))
      (node (ref "C4") (pin "1") (pinfunction "1_1") (pintype "passive"))
      (node (ref "J5") (pin "5") (pinfunction "5_5") (pintype "passive"))
      (node (ref "R10") (pin "2") (pinfunction "2_2") (pintype "passive"))
      (node (ref "R16") (pin "2") (pinfunction "2_2") (pintype "passive"))
      (node (ref "R2") (pin "2") (pinfunction "2_2") (pintype "passive"))
      (node (ref "R22") (pin "2") (pinfunction "2_2") (pintype "passive"))
      (node (ref "R28") (pin "2") (pinfunction "2_2") (pintype "passive"))
      (node (ref "R7") (pin "2") (pinfunction "2_2") (pintype "passive"))
      (node (ref "R8") (pin "2") (pinfunction "2_2") (pintype "passive"))
      (node (ref "R9") (pin "2") (pinfunction "2_2") (pintype "passive"))
      (node (ref "TP11") (pin "1") (pinfunction "1_1") (pintype "passive"))
      (node (ref "U1") (pin "8") (pinfunction "VCC_8") (pintype "power_in"))
      (node (ref "U2") (pin "1") (pinfunction "VCCA_1") (pintype "power_in"))
      (node (ref "U2") (pin "15") (pinfunction "T/~{R}1_15") (pintype "input"))
      (node (ref "U2") (pin "2") (pinfunction "T/~{R}0_2") (pintype "input"))
      (node (ref "U3") (pin "17") (pinfunction "VDDIOB18_17") (pintype "power_in"))
      (node (ref "U3") (pin "26") (pinfunction "VDDIOB18_26") (pintype "power_in"))
      (node (ref "U3") (pin "31") (pinfunction "USB_VDD18_31") (pintype "power_in"))
      (node (ref "U3") (pin "38") (pinfunction "VDDIOR_38") (pintype "power_in"))
      (node (ref "U3") (pin "52") (pinfunction "VDDIOT_52") (pintype "power_in"))
      (node (ref "U3") (pin "8") (pinfunction "VDDIOL_8") (pintype "power_in"))
      (node (ref "U4") (pin "1") (pinfunction "VCCA_1") (pintype "power_in"))
      (node (ref "U4") (pin "15") (pinfunction "T/~{R}1_15") (pintype "input"))
      (node (ref "U4") (pin "2") (pinfunction "T/~{R}0_2") (pintype "input"))
      (node (ref "U4") (pin "7") (pinfunction "T/~{R}3_7") (pintype "input"))
      (node (ref "U5") (pin "6") (pinfunction "VCC_6") (pintype "power_in"))
      (node (ref "U6") (pin "2") (pinfunction "OUT2_2") (pintype "power_in"))
    )
    (net (code "42") (name "3V3X") (class "Default")
      (node (ref "C19") (pin "1") (pinfunction "1_1") (pintype "passive"))
      (node (ref "U2") (pin "16") (pinfunction "VCCB_16") (pintype "power_in"))
    )
    (net (code "43") (name "3V3_DBG") (class "Default")
      (node (ref "C13") (pin "1") (pinfunction "1_1") (pintype "passive"))
      (node (ref "C35") (pin "1") (pinfunction "1_1") (pintype "passive"))
      (node (ref "D1") (pin "1") (pinfunction "GRN_A_1") (pintype "passive"))
      (node (ref "D1") (pin "2") (pinfunction "RED_A_2") (pintype "passive"))
      (node (ref "D3") (pin "1") (pinfunction "GRN_A_1") (pintype "passive"))
      (node (ref "D3") (pin "2") (pinfunction "RED_A_2") (pintype "passive"))
      (node (ref "R26") (pin "2") (pinfunction "2_2") (pintype "passive"))
      (node (ref "TP9") (pin "1") (pinfunction "1_1") (pintype "passive"))
      (node (ref "U3") (pin "30") (pinfunction "USB_VDD33_30") (pintype "power_in"))
      (node (ref "U6") (pin "1") (pinfunction "OUT1_1") (pintype "power_in"))
    )
    (net (code "44") (name "5V_DBG") (class "Default")
      (node (ref "C14") (pin "1") (pinfunction "1_1") (pintype "passive"))
      (node (ref "C3") (pin "1") (pinfunction "1_1") (pintype "passive"))
      (node (ref "C36") (pin "1") (pinfunction "1_1") (pintype "passive"))
      (node (ref "FB1") (pin "2") (pinfunction "2_2") (pintype "passive"))
      (node (ref "TP10") (pin "1") (pinfunction "1_1") (pintype "passive"))
      (node (ref "U6") (pin "4") (pinfunction "EN2_4") (pintype "input"))
      (node (ref "U6") (pin "5") (pinfunction "IN_5") (pintype "power_in"))
      (node (ref "U6") (pin "6") (pinfunction "EN1_6") (pintype "input"))
      (node (ref "U7") (pin "3") (pinfunction "VIN_3") (pintype "power_in"))
      (node (ref "U7") (pin "5") (pinfunction "EN_5") (pintype "input"))
    )
    (net (code "45") (name "GND") (class "Default")
      (node (ref "C1") (pin "2") (pinfunction "2_2") (pintype "passive"))
      (node (ref "C11") (pin "2") (pinfunction "2_2") (pintype "passive"))
      (node (ref "C12") (pin "2") (pinfunction "2_2") (pintype "passive"))
      (node (ref "C13") (pin "2") (pinfunction "2_2") (pintype "passive"))
      (node (ref "C14") (pin "2") (pinfunction "2_2") (pintype "passive"))
      (node (ref "C15") (pin "2") (pinfunction "2_2") (pintype "passive"))
      (node (ref "C16") (pin "2") (pinfunction "2_2") (pintype "passive"))
      (node (ref "C17") (pin "2") (pinfunction "2_2") (pintype "passive"))
      (node (ref "C18") (pin "2") (pinfunction "2_2") (pintype "passive"))
      (node (ref "C19") (pin "2") (pinfunction "2_2") (pintype "passive"))
      (node (ref "C2") (pin "2") (pinfunction "2_2") (pintype "passive"))
      (node (ref "C20") (pin "2") (pinfunction "2_2") (pintype "passive"))
      (node (ref "C21") (pin "2") (pinfunction "2_2") (pintype "passive"))
      (node (ref "C22") (pin "2") (pinfunction "2_2") (pintype "passive"))
      (node (ref "C23") (pin "2") (pinfunction "2_2") (pintype "passive"))
      (node (ref "C24") (pin "2") (pinfunction "2_2") (pintype "passive"))
      (node (ref "C25") (pin "2") (pinfunction "2_2") (pintype "passive"))
      (node (ref "C26") (pin "2") (pinfunction "2_2") (pintype "passive"))
      (node (ref "C27") (pin "2") (pinfunction "2_2") (pintype "passive"))
      (node (ref "C28") (pin "2") (pinfunction "2_2") (pintype "passive"))
      (node (ref "C29") (pin "2") (pinfunction "2_2") (pintype "passive"))
      (node (ref "C3") (pin "2") (pinfunction "2_2") (pintype "passive"))
      (node (ref "C30") (pin "2") (pinfunction "2_2") (pintype "passive"))
      (node (ref "C31") (pin "2") (pinfunction "2_2") (pintype "passive"))
      (node (ref "C32") (pin "2") (pinfunction "2_2") (pintype "passive"))
      (node (ref "C33") (pin "2") (pinfunction "2_2") (pintype "passive"))
      (node (ref "C34") (pin "2") (pinfunction "2_2") (pintype "passive"))
      (node (ref "C35") (pin "2") (pinfunction "2_2") (pintype "passive"))
      (node (ref "C36") (pin "2") (pinfunction "2_2") (pintype "passive"))
      (node (ref "C38") (pin "2") (pinfunction "2_2") (pintype "passive"))
      (node (ref "C4") (pin "2") (pinfunction "2_2") (pintype "passive"))
      (node (ref "C5") (pin "2") (pinfunction "2_2") (pintype "passive"))
      (node (ref "D2") (pin "2") (pinfunction "2_2") (pintype "passive"))
      (node (ref "J2") (pin "5") (pinfunction "GND_5") (pintype "passive"))
      (node (ref "J2") (pin "S1") (pinfunction "S1_S1") (pintype "passive"))
      (node (ref "J2") (pin "S2") (pinfunction "S2_S2") (pintype "passive"))
      (node (ref "J2") (pin "S3") (pinfunction "S3_S3") (pintype "passive"))
      (node (ref "J2") (pin "S4") (pinfunction "S4_S4") (pintype "passive"))
      (node (ref "J2") (pin "S5") (pinfunction "S5_S5") (pintype "passive"))
      (node (ref "J2") (pin "S6") (pinfunction "S6_S6") (pintype "passive"))
      (node (ref "J5") (pin "2") (pinfunction "2_2") (pintype "passive"))
      (node (ref "R17") (pin "1") (pinfunction "1_1") (pintype "passive"))
      (node (ref "R26") (pin "1") (pinfunction "1_1") (pintype "passive"))
      (node (ref "R28") (pin "1") (pinfunction "1_1") (pintype "passive"))
      (node (ref "R30") (pin "1") (pinfunction "1_1") (pintype "passive"))
      (node (ref "R4") (pin "1") (pinfunction "1_1") (pintype "passive"))
      (node (ref "R5") (pin "1") (pinfunction "1_1") (pintype "passive"))
      (node (ref "R6") (pin "1") (pinfunction "1_1") (pintype "passive"))
      (node (ref "R6") (pin "2") (pinfunction "2_2") (pintype "passive"))
      (node (ref "R6") (pin "3") (pinfunction "3_3") (pintype "passive"))
      (node (ref "R6") (pin "4") (pinfunction "4_4") (pintype "passive"))
      (node (ref "TP13") (pin "1") (pinfunction "1_1") (pintype "passive"))
      (node (ref "TP14") (pin "1") (pinfunction "1_1") (pintype "passive"))
      (node (ref "TP15") (pin "1") (pinfunction "1_1") (pintype "passive"))
      (node (ref "U1") (pin "4") (pinfunction "GND_4") (pintype "power_in"))
      (node (ref "U2") (pin "10") (pinfunction "T/~{R}2_10") (pintype "input"))
      (node (ref "U2") (pin "17") (pinfunction "PAD_17") (pintype "power_in"))
      (node (ref "U2") (pin "7") (pinfunction "T/~{R}3_7") (pintype "input"))
      (node (ref "U2") (pin "8") (pinfunction "GND_8") (pintype "power_in"))
      (node (ref "U3") (pin "65") (pinfunction "GND_65") (pintype "power_in"))
      (node (ref "U4") (pin "10") (pinfunction "T/~{R}2_10") (pintype "input"))
      (node (ref "U4") (pin "17") (pinfunction "PAD_17") (pintype "power_in"))
      (node (ref "U4") (pin "8") (pinfunction "GND_8") (pintype "power_in"))
      (node (ref "U5") (pin "2") (pinfunction "A_2") (pintype "input"))
      (node (ref "U5") (pin "3") (pinfunction "GND_3") (pintype "power_in"))
      (node (ref "U6") (pin "3") (pinfunction "GND_3") (pintype "power_in"))
      (node (ref "U6") (pin "7") (pinfunction "PAD_7") (pintype "power_in"))
      (node (ref "U7") (pin "2") (pinfunction "GND_2") (pintype "power_in"))
      (node (ref "X1") (pin "2") (pinfunction "CASE_2_2") (pintype "passive"))
      (node (ref "X1") (pin "4") (pinfunction "CASE_4_4") (pintype "passive"))
    )
    (net (code "46") (name "Net-(D1-GRN_K)") (class "Default")
      (node (ref "D1") (pin "3") (pinfunction "GRN_K_3") (pintype "passive"))
      (node (ref "R1") (pin "7") (pinfunction "7_7") (pintype "passive"))
    )
    (net (code "47") (name "Net-(D1-RED_K)") (class "Default")
      (node (ref "D1") (pin "4") (pinfunction "RED_K_4") (pintype "passive"))
      (node (ref "R1") (pin "8") (pinfunction "8_8") (pintype "passive"))
    )
    (net (code "48") (name "Net-(D3-GRN_K)") (class "Default")
      (node (ref "D3") (pin "3") (pinfunction "GRN_K_3") (pintype "passive"))
      (node (ref "R1") (pin "5") (pinfunction "5_5") (pintype "passive"))
    )
    (net (code "49") (name "Net-(D3-RED_K)") (class "Default")
      (node (ref "D3") (pin "4") (pinfunction "RED_K_4") (pintype "passive"))
      (node (ref "R1") (pin "6") (pinfunction "6_6") (pintype "passive"))
    )
    (net (code "50") (name "Net-(F1-T2)") (class "Default")
      (node (ref "F1") (pin "2") (pinfunction "T2_2") (pintype "passive"))
      (node (ref "FB1") (pin "1") (pinfunction "1_1") (pintype "passive"))
    )
    (net (code "51") (name "Net-(U2-B0)") (class "Default")
      (node (ref "R3") (pin "1") (pinfunction "1_1") (pintype "passive"))
      (node (ref "U2") (pin "14") (pinfunction "B0_14") (pintype "bidirectional"))
    )
    (net (code "52") (name "Net-(U2-B1)") (class "Default")
      (node (ref "R3") (pin "2") (pinfunction "2_2") (pintype "passive"))
      (node (ref "U2") (pin "13") (pinfunction "B1_13") (pintype "bidirectional"))
    )
    (net (code "53") (name "Net-(U2-B2)") (class "Default")
      (node (ref "R3") (pin "3") (pinfunction "3_3") (pintype "passive"))
      (node (ref "U2") (pin "12") (pinfunction "B2_12") (pintype "bidirectional"))
    )
    (net (code "54") (name "Net-(U2-B3)") (class "Default")
      (node (ref "R3") (pin "4") (pinfunction "4_4") (pintype "passive"))
      (node (ref "U2") (pin "11") (pinfunction "B3_11") (pintype "bidirectional"))
    )
    (net (code "55") (name "Net-(U3-PLL_AVDD)") (class "Default")
      (node (ref "C5") (pin "1") (pinfunction "1_1") (pintype "passive"))
      (node (ref "FB2") (pin "1") (pinfunction "1_1") (pintype "passive"))
      (node (ref "U3") (pin "22") (pinfunction "PLL_AVDD_22") (pintype "power_in"))
    )
    (net (code "56") (name "Net-(U3-X0D29)") (class "Default")
      (node (ref "TP1") (pin "1") (pinfunction "1_1") (pintype "passive"))
      (node (ref "U3") (pin "40") (pinfunction "X0D29_40") (pintype "bidirectional"))
    )
    (net (code "57") (name "Net-(U3-XIN)") (class "Default")
      (node (ref "C11") (pin "1") (pinfunction "1_1") (pintype "passive"))
      (node (ref "R19") (pin "1") (pinfunction "1_1") (pintype "passive"))
      (node (ref "U3") (pin "16") (pinfunction "XIN_16") (pintype "passive"))
      (node (ref "X1") (pin "1") (pinfunction "A_1") (pintype "passive"))
    )
    (net (code "58") (name "Net-(U3-XOUT)") (class "Default")
      (node (ref "R19") (pin "2") (pinfunction "2_2") (pintype "passive"))
      (node (ref "R21") (pin "2") (pinfunction "2_2") (pintype "passive"))
      (node (ref "U3") (pin "15") (pinfunction "XOUT_15") (pintype "passive"))
    )
    (net (code "59") (name "Net-(U4-B0)") (class "Default")
      (node (ref "R14") (pin "1") (pinfunction "1_1") (pintype "passive"))
      (node (ref "U4") (pin "14") (pinfunction "B0_14") (pintype "bidirectional"))
    )
    (net (code "60") (name "Net-(U4-B1)") (class "Default")
      (node (ref "R14") (pin "2") (pinfunction "2_2") (pintype "passive"))
      (node (ref "U4") (pin "13") (pinfunction "B1_13") (pintype "bidirectional"))
    )
    (net (code "61") (name "Net-(U4-B2)") (class "Default")
      (node (ref "R14") (pin "3") (pinfunction "3_3") (pintype "passive"))
      (node (ref "U4") (pin "12") (pinfunction "B2_12") (pintype "bidirectional"))
    )
    (net (code "62") (name "Net-(U4-B3)") (class "Default")
      (node (ref "R14") (pin "4") (pinfunction "4_4") (pintype "passive"))
      (node (ref "U4") (pin "11") (pinfunction "B3_11") (pintype "bidirectional"))
    )
    (net (code "63") (name "Net-(U7-FB)") (class "Default")
      (node (ref "C37") (pin "2") (pinfunction "2_2") (pintype "passive"))
      (node (ref "R29") (pin "1") (pinfunction "1_1") (pintype "passive"))
      (node (ref "R30") (pin "2") (pinfunction "2_2") (pintype "passive"))
      (node (ref "R31") (pin "2") (pinfunction "2_2") (pintype "passive"))
      (node (ref "U7") (pin "1") (pinfunction "FB_1") (pintype "passive"))
    )
    (net (code "64") (name "Net-(U7-SW)") (class "Default")
      (node (ref "L1") (pin "1") (pinfunction "1_1") (pintype "passive"))
      (node (ref "U7") (pin "4") (pinfunction "SW_4") (pintype "passive"))
    )
    (net (code "65") (name "Net-(X1-B)") (class "Default")
      (node (ref "C12") (pin "1") (pinfunction "1_1") (pintype "passive"))
      (node (ref "R21") (pin "1") (pinfunction "1_1") (pintype "passive"))
      (node (ref "X1") (pin "3") (pinfunction "B_3") (pintype "passive"))
    )
    (net (code "66") (name "unconnected-(D2-Pad3)") (class "Default")
      (node (ref "D2") (pin "3") (pinfunction "3_3") (pintype "passive+no_connect"))
    )
    (net (code "67") (name "unconnected-(D2-Pad4)") (class "Default")
      (node (ref "D2") (pin "4") (pinfunction "4_4") (pintype "passive+no_connect"))
    )
    (net (code "68") (name "unconnected-(J2-ID-Pad4)") (class "Default")
      (node (ref "J2") (pin "4") (pinfunction "ID_4") (pintype "passive+no_connect"))
    )
    (net (code "69") (name "unconnected-(U1-PAD-Pad9)") (class "Default")
      (node (ref "U1") (pin "9") (pinfunction "PAD_9") (pintype "passive+no_connect"))
    )
    (net (code "70") (name "unconnected-(U3-NC-Pad25)") (class "Default")
      (node (ref "U3") (pin "25") (pinfunction "NC_25") (pintype "passive+no_connect"))
    )
    (net (code "71") (name "unconnected-(U3-X0D00-Pad6)") (class "Default")
      (node (ref "U3") (pin "6") (pinfunction "X0D00_6") (pintype "bidirectional+no_connect"))
    )
    (net (code "72") (name "unconnected-(U3-X0D30-Pad54)") (class "Default")
      (node (ref "U3") (pin "54") (pinfunction "X0D30_54") (pintype "bidirectional+no_connect"))
    )
    (net (code "73") (name "unconnected-(U3-X0D31-Pad55)") (class "Default")
      (node (ref "U3") (pin "55") (pinfunction "X0D31_55") (pintype "bidirectional+no_connect"))
    )
    (net (code "74") (name "unconnected-(U3-X0D32-Pad56)") (class "Default")
      (node (ref "U3") (pin "56") (pinfunction "X0D32_56") (pintype "bidirectional+no_connect"))
    )
    (net (code "75") (name "unconnected-(U3-X0D33-Pad58)") (class "Default")
      (node (ref "U3") (pin "58") (pinfunction "X0D33_58") (pintype "bidirectional+no_connect"))
    )
    (net (code "76") (name "unconnected-(U3-X1D00-Pad9)") (class "Default")
      (node (ref "U3") (pin "9") (pinfunction "X1D00_9") (pintype "bidirectional+no_connect"))
    )
    (net (code "77") (name "unconnected-(U3-X1D01-Pad10)") (class "Default")
      (node (ref "U3") (pin "10") (pinfunction "X1D01_10") (pintype "bidirectional+no_connect"))
    )
    (net (code "78") (name "unconnected-(U3-X1D09-Pad11)") (class "Default")
      (node (ref "U3") (pin "11") (pinfunction "X1D09_11") (pintype "bidirectional+no_connect"))
    )
    (net (code "79") (name "unconnected-(U3-X1D11-Pad14)") (class "Default")
      (node (ref "U3") (pin "14") (pinfunction "X1D11_14") (pintype "bidirectional+no_connect"))
    )
    (net (code "80") (name "unconnected-(U3-X1D13-Pad32)") (class "Default")
      (node (ref "U3") (pin "32") (pinfunction "X1D13_32") (pintype "bidirectional+no_connect"))
    )
    (net (code "81") (name "unconnected-(U3-X1D22-Pad39)") (class "Default")
      (node (ref "U3") (pin "39") (pinfunction "X1D22_39") (pintype "bidirectional+no_connect"))
    )
    (net (code "82") (name "unconnected-(U3-X1D34-Pad53)") (class "Default")
      (node (ref "U3") (pin "53") (pinfunction "X1D34_53") (pintype "bidirectional+no_connect"))
    )
    (net (code "83") (name "unconnected-(U5-NC-Pad5)") (class "Default")
      (node (ref "U5") (pin "5") (pinfunction "NC_5") (pintype "passive+no_connect"))
    )
    (net (code "84") (name "unconnected-(U7-PG-Pad6)") (class "Default")
      (node (ref "U7") (pin "6") (pinfunction "PG_6") (pintype "passive+no_connect"))
    )
  )
)
